# MCO23S17.net
KiCad netlist of a schematic drawn in Altium Designer
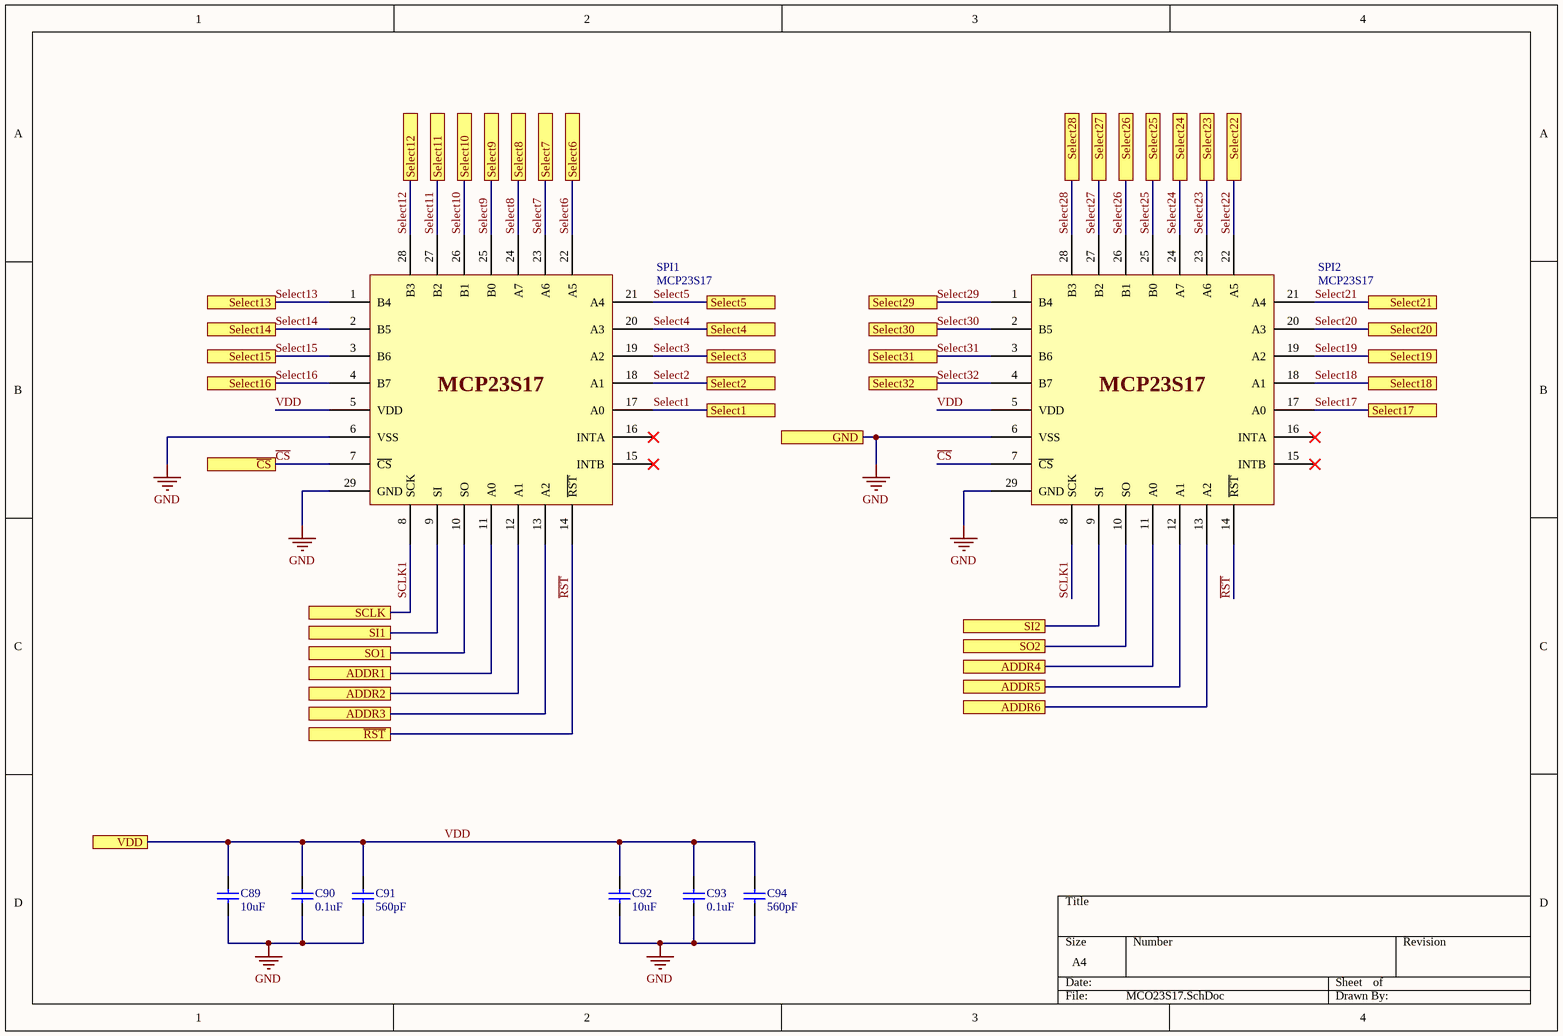
[diagram p0: MCO23S17.SchDoc]

(export (version "E")
  (design (tool "Eeschema 10.0.6"))
  (components
    (comp (ref "C89")
      (value "10uF")
      (footprint "CLS_Library:C0805")
      (description "Cap 10uF")
      (fields
        (field (name "MANUFACTURER") "Taiyo Yuden")
        (field (name "MANUFACTURER PART NUMBER") "UMK212SD103KD-T")
      )
      (libsource (lib "Chip1_TestBoard") (part "Cap 10uF"))
    )
    (comp (ref "C90")
      (value "0.1uF")
      (footprint "CLS_Library:C0805")
      (description "Cap 0.1uF")
      (fields
        (field (name "MANUFACTURER") "Taiyo Yuden")
        (field (name "MANUFACTURER PART NUMBER") "UMK212SD103KD-T")
      )
      (libsource (lib "Chip1_TestBoard") (part "Cap 0.1uF"))
    )
    (comp (ref "C91")
      (value "560pF")
      (footprint "CLS_Library:C0805")
      (description "Cap 560pF")
      (fields
        (field (name "MANUFACTURER") "Taiyo Yuden")
        (field (name "MANUFACTURER PART NUMBER") "UMK212SD103KD-T")
      )
      (libsource (lib "Chip1_TestBoard") (part "Cap 560pF"))
    )
    (comp (ref "C92")
      (value "10uF")
      (footprint "CLS_Library:C0805")
      (description "Cap 10uF")
      (fields
        (field (name "MANUFACTURER") "Taiyo Yuden")
        (field (name "MANUFACTURER PART NUMBER") "UMK212SD103KD-T")
      )
      (libsource (lib "Chip1_TestBoard") (part "Cap 10uF"))
    )
    (comp (ref "C93")
      (value "0.1uF")
      (footprint "CLS_Library:C0805")
      (description "Cap 0.1uF")
      (fields
        (field (name "MANUFACTURER") "Taiyo Yuden")
        (field (name "MANUFACTURER PART NUMBER") "UMK212SD103KD-T")
      )
      (libsource (lib "Chip1_TestBoard") (part "Cap 0.1uF"))
    )
    (comp (ref "C94")
      (value "560pF")
      (footprint "CLS_Library:C0805")
      (description "Cap 560pF")
      (fields
        (field (name "MANUFACTURER") "Taiyo Yuden")
        (field (name "MANUFACTURER PART NUMBER") "UMK212SD103KD-T")
      )
      (libsource (lib "Chip1_TestBoard") (part "Cap 560pF"))
    )
    (comp (ref "SPI1")
      (value "MCP23S17")
      (footprint "MCP23S17")
      (description "16b IO Expander with SPI")
      (libsource (lib "ICXTRAP1") (part "MCP23S17"))
    )
    (comp (ref "SPI2")
      (value "MCP23S17")
      (footprint "MCP23S17")
      (description "16b IO Expander with SPI")
      (libsource (lib "ICXTRAP1") (part "MCP23S17"))
    )
  )
  (nets
    (net (code "1") (name "/ADDR1") (class "Default")
      (node (ref "SPI1") (pin "11") (pinfunction "A0_11") (pintype "passive"))
    )
    (net (code "2") (name "/ADDR2") (class "Default")
      (node (ref "SPI1") (pin "12") (pinfunction "A1_12") (pintype "passive"))
    )
    (net (code "3") (name "/ADDR3") (class "Default")
      (node (ref "SPI1") (pin "13") (pinfunction "A2_13") (pintype "passive"))
    )
    (net (code "4") (name "/ADDR4") (class "Default")
      (node (ref "SPI2") (pin "11") (pinfunction "A0_11") (pintype "passive"))
    )
    (net (code "5") (name "/ADDR5") (class "Default")
      (node (ref "SPI2") (pin "12") (pinfunction "A1_12") (pintype "passive"))
    )
    (net (code "6") (name "/ADDR6") (class "Default")
      (node (ref "SPI2") (pin "13") (pinfunction "A2_13") (pintype "passive"))
    )
    (net (code "7") (name "/SCLK1") (class "Default")
      (node (ref "SPI1") (pin "8") (pinfunction "SCK_8") (pintype "passive"))
      (node (ref "SPI2") (pin "8") (pinfunction "SCK_8") (pintype "passive"))
    )
    (net (code "8") (name "/SI1") (class "Default")
      (node (ref "SPI1") (pin "9") (pinfunction "SI_9") (pintype "passive"))
    )
    (net (code "9") (name "/SI2") (class "Default")
      (node (ref "SPI2") (pin "9") (pinfunction "SI_9") (pintype "passive"))
    )
    (net (code "10") (name "/SO1") (class "Default")
      (node (ref "SPI1") (pin "10") (pinfunction "SO_10") (pintype "passive"))
    )
    (net (code "11") (name "/SO2") (class "Default")
      (node (ref "SPI2") (pin "10") (pinfunction "SO_10") (pintype "passive"))
    )
    (net (code "12") (name "/Select1") (class "Default")
      (node (ref "SPI1") (pin "17") (pinfunction "A0_17") (pintype "passive"))
    )
    (net (code "13") (name "/Select2") (class "Default")
      (node (ref "SPI1") (pin "18") (pinfunction "A1_18") (pintype "passive"))
    )
    (net (code "14") (name "/Select3") (class "Default")
      (node (ref "SPI1") (pin "19") (pinfunction "A2_19") (pintype "passive"))
    )
    (net (code "15") (name "/Select4") (class "Default")
      (node (ref "SPI1") (pin "20") (pinfunction "A3_20") (pintype "passive"))
    )
    (net (code "16") (name "/Select5") (class "Default")
      (node (ref "SPI1") (pin "21") (pinfunction "A4_21") (pintype "passive"))
    )
    (net (code "17") (name "/Select6") (class "Default")
      (node (ref "SPI1") (pin "22") (pinfunction "A5_22") (pintype "passive"))
    )
    (net (code "18") (name "/Select7") (class "Default")
      (node (ref "SPI1") (pin "23") (pinfunction "A6_23") (pintype "passive"))
    )
    (net (code "19") (name "/Select8") (class "Default")
      (node (ref "SPI1") (pin "24") (pinfunction "A7_24") (pintype "passive"))
    )
    (net (code "20") (name "/Select9") (class "Default")
      (node (ref "SPI1") (pin "25") (pinfunction "B0_25") (pintype "passive"))
    )
    (net (code "21") (name "/Select10") (class "Default")
      (node (ref "SPI1") (pin "26") (pinfunction "B1_26") (pintype "passive"))
    )
    (net (code "22") (name "/Select11") (class "Default")
      (node (ref "SPI1") (pin "27") (pinfunction "B2_27") (pintype "passive"))
    )
    (net (code "23") (name "/Select12") (class "Default")
      (node (ref "SPI1") (pin "28") (pinfunction "B3_28") (pintype "passive"))
    )
    (net (code "24") (name "/Select13") (class "Default")
      (node (ref "SPI1") (pin "1") (pinfunction "B4_1") (pintype "passive"))
    )
    (net (code "25") (name "/Select14") (class "Default")
      (node (ref "SPI1") (pin "2") (pinfunction "B5_2") (pintype "passive"))
    )
    (net (code "26") (name "/Select15") (class "Default")
      (node (ref "SPI1") (pin "3") (pinfunction "B6_3") (pintype "passive"))
    )
    (net (code "27") (name "/Select16") (class "Default")
      (node (ref "SPI1") (pin "4") (pinfunction "B7_4") (pintype "passive"))
    )
    (net (code "28") (name "/Select17") (class "Default")
      (node (ref "SPI2") (pin "17") (pinfunction "A0_17") (pintype "passive"))
    )
    (net (code "29") (name "/Select18") (class "Default")
      (node (ref "SPI2") (pin "18") (pinfunction "A1_18") (pintype "passive"))
    )
    (net (code "30") (name "/Select19") (class "Default")
      (node (ref "SPI2") (pin "19") (pinfunction "A2_19") (pintype "passive"))
    )
    (net (code "31") (name "/Select20") (class "Default")
      (node (ref "SPI2") (pin "20") (pinfunction "A3_20") (pintype "passive"))
    )
    (net (code "32") (name "/Select21") (class "Default")
      (node (ref "SPI2") (pin "21") (pinfunction "A4_21") (pintype "passive"))
    )
    (net (code "33") (name "/Select22") (class "Default")
      (node (ref "SPI2") (pin "22") (pinfunction "A5_22") (pintype "passive"))
    )
    (net (code "34") (name "/Select23") (class "Default")
      (node (ref "SPI2") (pin "23") (pinfunction "A6_23") (pintype "passive"))
    )
    (net (code "35") (name "/Select24") (class "Default")
      (node (ref "SPI2") (pin "24") (pinfunction "A7_24") (pintype "passive"))
    )
    (net (code "36") (name "/Select25") (class "Default")
      (node (ref "SPI2") (pin "25") (pinfunction "B0_25") (pintype "passive"))
    )
    (net (code "37") (name "/Select26") (class "Default")
      (node (ref "SPI2") (pin "26") (pinfunction "B1_26") (pintype "passive"))
    )
    (net (code "38") (name "/Select27") (class "Default")
      (node (ref "SPI2") (pin "27") (pinfunction "B2_27") (pintype "passive"))
    )
    (net (code "39") (name "/Select28") (class "Default")
      (node (ref "SPI2") (pin "28") (pinfunction "B3_28") (pintype "passive"))
    )
    (net (code "40") (name "/Select29") (class "Default")
      (node (ref "SPI2") (pin "1") (pinfunction "B4_1") (pintype "passive"))
    )
    (net (code "41") (name "/Select30") (class "Default")
      (node (ref "SPI2") (pin "2") (pinfunction "B5_2") (pintype "passive"))
    )
    (net (code "42") (name "/Select31") (class "Default")
      (node (ref "SPI2") (pin "3") (pinfunction "B6_3") (pintype "passive"))
    )
    (net (code "43") (name "/Select32") (class "Default")
      (node (ref "SPI2") (pin "4") (pinfunction "B7_4") (pintype "passive"))
    )
    (net (code "44") (name "/VDD") (class "Default")
      (node (ref "C89") (pin "2") (pinfunction "2_2") (pintype "passive"))
      (node (ref "C90") (pin "2") (pinfunction "2_2") (pintype "passive"))
      (node (ref "C91") (pin "2") (pinfunction "2_2") (pintype "passive"))
      (node (ref "C92") (pin "2") (pinfunction "2_2") (pintype "passive"))
      (node (ref "C93") (pin "2") (pinfunction "2_2") (pintype "passive"))
      (node (ref "C94") (pin "2") (pinfunction "2_2") (pintype "passive"))
      (node (ref "SPI1") (pin "5") (pinfunction "VDD_5") (pintype "passive"))
      (node (ref "SPI2") (pin "5") (pinfunction "VDD_5") (pintype "passive"))
    )
    (net (code "45") (name "/~{CS}") (class "Default")
      (node (ref "SPI1") (pin "7") (pinfunction "~{CS}_7") (pintype "passive"))
      (node (ref "SPI2") (pin "7") (pinfunction "~{CS}_7") (pintype "passive"))
    )
    (net (code "46") (name "/~{RST}") (class "Default")
      (node (ref "SPI1") (pin "14") (pinfunction "~{RST}_14") (pintype "passive"))
      (node (ref "SPI2") (pin "14") (pinfunction "~{RST}_14") (pintype "passive"))
    )
    (net (code "47") (name "GND") (class "Default")
      (node (ref "C89") (pin "1") (pinfunction "1_1") (pintype "passive"))
      (node (ref "C90") (pin "1") (pinfunction "1_1") (pintype "passive"))
      (node (ref "C91") (pin "1") (pinfunction "1_1") (pintype "passive"))
      (node (ref "C92") (pin "1") (pinfunction "1_1") (pintype "passive"))
      (node (ref "C93") (pin "1") (pinfunction "1_1") (pintype "passive"))
      (node (ref "C94") (pin "1") (pinfunction "1_1") (pintype "passive"))
      (node (ref "SPI1") (pin "29") (pinfunction "GND_29") (pintype "passive"))
      (node (ref "SPI1") (pin "6") (pinfunction "VSS_6") (pintype "passive"))
      (node (ref "SPI2") (pin "29") (pinfunction "GND_29") (pintype "passive"))
      (node (ref "SPI2") (pin "6") (pinfunction "VSS_6") (pintype "passive"))
    )
    (net (code "48") (name "unconnected-(SPI1-INTA-Pad16)") (class "Default")
      (node (ref "SPI1") (pin "16") (pinfunction "INTA_16") (pintype "passive+no_connect"))
    )
    (net (code "49") (name "unconnected-(SPI1-INTB-Pad15)") (class "Default")
      (node (ref "SPI1") (pin "15") (pinfunction "INTB_15") (pintype "passive+no_connect"))
    )
    (net (code "50") (name "unconnected-(SPI2-INTA-Pad16)") (class "Default")
      (node (ref "SPI2") (pin "16") (pinfunction "INTA_16") (pintype "passive+no_connect"))
    )
    (net (code "51") (name "unconnected-(SPI2-INTB-Pad15)") (class "Default")
      (node (ref "SPI2") (pin "15") (pinfunction "INTB_15") (pintype "passive+no_connect"))
    )
  )
)
